# Schaltplan.net
KiCad netlist of a schematic drawn in EAGLE
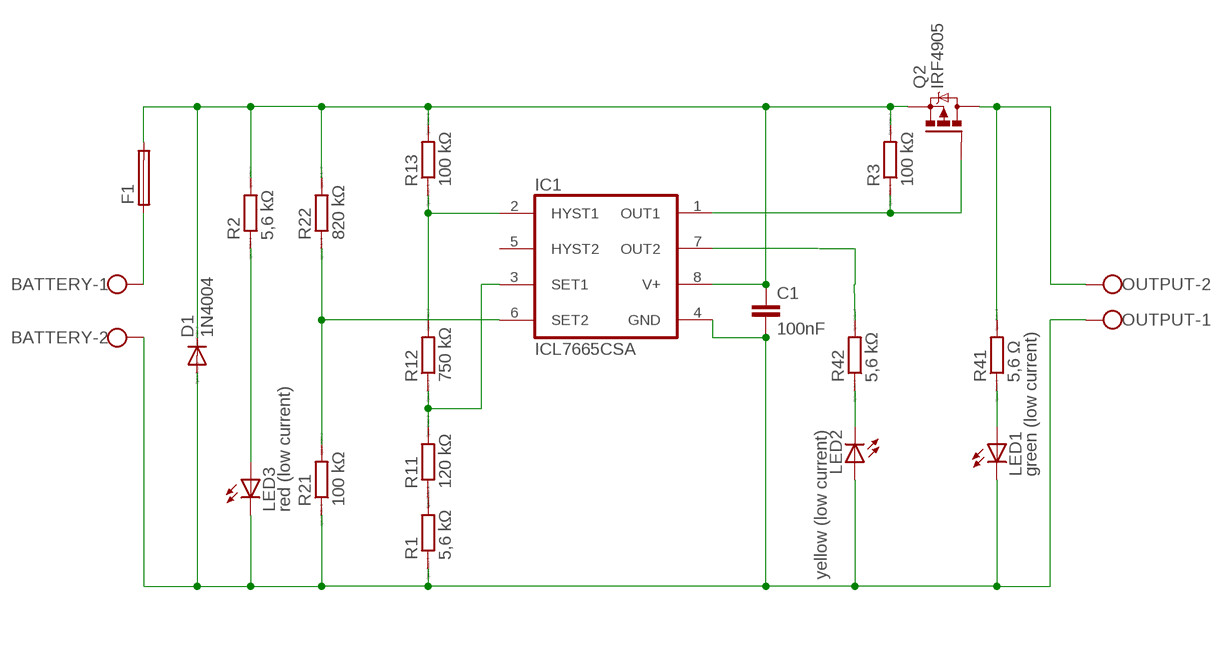
[diagram p0: schematic, sheet 1]

(export (version "E")
  (design (tool "Eeschema 10.0.6"))
  (components
    (comp (ref "BATTERY")
      (value "W237-102")
      (footprint "eagle-import:W237-102")
      (fields (field (name "MPN") "237-102"))
      (libsource (lib "eagle-import") (part "W237-102"))
    )
    (comp (ref "C1")
      (value "100nF")
      (footprint "eagle-import:C0603")
      (libsource (lib "eagle-import") (part "C-EUC0603"))
    )
    (comp (ref "D1")
      (value "1N4004")
      (footprint "eagle-import:DO41-10")
      (libsource (lib "eagle-import") (part "1N4004"))
    )
    (comp (ref "F1")
      (value "GSH15")
      (footprint "eagle-import:GSH15")
      (fields (field (name "MPN") "64900001039"))
      (libsource (lib "eagle-import") (part "GSH15"))
    )
    (comp (ref "IC1")
      (value "ICL7665CSA")
      (footprint "eagle-import:SO08")
      (fields (field (name "MPN") "ICL7665CSA+"))
      (libsource (lib "eagle-import") (part "ICL7665CSA"))
    )
    (comp (ref "LED1")
      (value "green (low current)")
      (footprint "eagle-import:SML0603")
      (libsource (lib "eagle-import") (part "LEDSML0603"))
    )
    (comp (ref "LED2")
      (value "yellow (low current)")
      (footprint "eagle-import:KA-3528ASYC")
      (libsource (lib "eagle-import") (part "LEDKA-3528ASYC"))
    )
    (comp (ref "LED3")
      (value "red (low current)")
      (footprint "eagle-import:KA-3528ASYC")
      (libsource (lib "eagle-import") (part "LEDKA-3528ASYC"))
    )
    (comp (ref "OUTPUT")
      (value "W237-102")
      (footprint "eagle-import:W237-102")
      (fields (field (name "MPN") "237-102"))
      (libsource (lib "eagle-import") (part "W237-102"))
    )
    (comp (ref "Q2")
      (value "IRF4905")
      (footprint "eagle-import:TO220BH")
      (libsource (lib "eagle-import") (part "IRF4905"))
    )
    (comp (ref "R1")
      (value "5,6 kΩ")
      (footprint "eagle-import:R1206")
      (libsource (lib "eagle-import") (part "RR1206"))
    )
    (comp (ref "R2")
      (value "5,6 kΩ")
      (footprint "eagle-import:R1206")
      (libsource (lib "eagle-import") (part "RR1206"))
    )
    (comp (ref "R3")
      (value "100 kΩ")
      (footprint "eagle-import:R1206")
      (libsource (lib "eagle-import") (part "RR1206"))
    )
    (comp (ref "R11")
      (value "120 kΩ")
      (footprint "eagle-import:R1206")
      (libsource (lib "eagle-import") (part "RR1206"))
    )
    (comp (ref "R12")
      (value "750 kΩ")
      (footprint "eagle-import:R1206")
      (libsource (lib "eagle-import") (part "RR1206"))
    )
    (comp (ref "R13")
      (value "100 kΩ")
      (footprint "eagle-import:R1206")
      (libsource (lib "eagle-import") (part "RR1206"))
    )
    (comp (ref "R21")
      (value "100 kΩ")
      (footprint "eagle-import:R1206")
      (libsource (lib "eagle-import") (part "RR1206"))
    )
    (comp (ref "R22")
      (value "820 kΩ")
      (footprint "eagle-import:R1206")
      (libsource (lib "eagle-import") (part "RR1206"))
    )
    (comp (ref "R41")
      (value "5,6 Ω")
      (footprint "eagle-import:R1206")
      (libsource (lib "eagle-import") (part "RR1206"))
    )
    (comp (ref "R42")
      (value "5,6 kΩ")
      (footprint "eagle-import:R1206")
      (libsource (lib "eagle-import") (part "RR1206"))
    )
  )
  (nets
    (net (code "1") (name "Net-(BATTERYA-KL)") (class "Default")
      (node (ref "BATTERY") (pin "1") (pinfunction "KL_1") (pintype "passive"))
      (node (ref "F1") (pin "1") (pinfunction "1_1") (pintype "passive"))
    )
    (net (code "2") (name "Net-(BATTERYB-KL)") (class "Default")
      (node (ref "BATTERY") (pin "2") (pinfunction "KL_2") (pintype "passive"))
      (node (ref "C1") (pin "2") (pinfunction "2_2") (pintype "passive"))
      (node (ref "D1") (pin "A") (pinfunction "A_A") (pintype "passive"))
      (node (ref "IC1") (pin "4") (pinfunction "GND_4") (pintype "power_in"))
      (node (ref "LED1") (pin "C") (pinfunction "C_C") (pintype "passive"))
      (node (ref "LED2") (pin "A") (pinfunction "A_A") (pintype "passive"))
      (node (ref "LED3") (pin "C") (pinfunction "C_C") (pintype "passive"))
      (node (ref "OUTPUT") (pin "1") (pinfunction "KL_1") (pintype "passive"))
      (node (ref "R1") (pin "1") (pinfunction "1_1") (pintype "passive"))
      (node (ref "R21") (pin "1") (pinfunction "1_1") (pintype "passive"))
    )
    (net (code "3") (name "Net-(IC1-HYST1)") (class "Default")
      (node (ref "IC1") (pin "2") (pinfunction "HYST1_2") (pintype "input"))
      (node (ref "R12") (pin "2") (pinfunction "2_2") (pintype "passive"))
      (node (ref "R13") (pin "1") (pinfunction "1_1") (pintype "passive"))
    )
    (net (code "4") (name "Net-(IC1-OUT1)") (class "Default")
      (node (ref "IC1") (pin "1") (pinfunction "OUT1_1") (pintype "output"))
      (node (ref "Q2") (pin "G") (pinfunction "G_G") (pintype "passive"))
      (node (ref "R3") (pin "1") (pinfunction "1_1") (pintype "passive"))
    )
    (net (code "5") (name "Net-(IC1-SET1)") (class "Default")
      (node (ref "IC1") (pin "3") (pinfunction "SET1_3") (pintype "input"))
      (node (ref "R11") (pin "2") (pinfunction "2_2") (pintype "passive"))
      (node (ref "R12") (pin "1") (pinfunction "1_1") (pintype "passive"))
    )
    (net (code "6") (name "Net-(IC1-SET2)") (class "Default")
      (node (ref "IC1") (pin "6") (pinfunction "SET2_6") (pintype "input"))
      (node (ref "R21") (pin "2") (pinfunction "2_2") (pintype "passive"))
      (node (ref "R22") (pin "1") (pinfunction "1_1") (pintype "passive"))
    )
    (net (code "7") (name "Net-(IC1-V+)") (class "Default")
      (node (ref "C1") (pin "1") (pinfunction "1_1") (pintype "passive"))
      (node (ref "D1") (pin "C") (pinfunction "C_C") (pintype "passive"))
      (node (ref "F1") (pin "2") (pinfunction "2_2") (pintype "passive"))
      (node (ref "IC1") (pin "8") (pinfunction "V+_8") (pintype "power_in"))
      (node (ref "Q2") (pin "S") (pinfunction "S_S") (pintype "passive"))
      (node (ref "R13") (pin "2") (pinfunction "2_2") (pintype "passive"))
      (node (ref "R2") (pin "2") (pinfunction "2_2") (pintype "passive"))
      (node (ref "R22") (pin "2") (pinfunction "2_2") (pintype "passive"))
      (node (ref "R3") (pin "2") (pinfunction "2_2") (pintype "passive"))
    )
    (net (code "8") (name "Net-(LED1-PadA)") (class "Default")
      (node (ref "LED1") (pin "A") (pinfunction "A_A") (pintype "passive"))
      (node (ref "R41") (pin "1") (pinfunction "1_1") (pintype "passive"))
    )
    (net (code "9") (name "Net-(LED2-PadC)") (class "Default")
      (node (ref "LED2") (pin "C") (pinfunction "C_C") (pintype "passive"))
      (node (ref "R42") (pin "1") (pinfunction "1_1") (pintype "passive"))
    )
    (net (code "10") (name "Net-(LED3-PadA)") (class "Default")
      (node (ref "LED3") (pin "A") (pinfunction "A_A") (pintype "passive"))
      (node (ref "R2") (pin "1") (pinfunction "1_1") (pintype "passive"))
    )
    (net (code "11") (name "Net-(OUTPUTB-KL)") (class "Default")
      (node (ref "OUTPUT") (pin "2") (pinfunction "KL_2") (pintype "passive"))
      (node (ref "Q2") (pin "D") (pinfunction "D_D") (pintype "passive"))
      (node (ref "R41") (pin "2") (pinfunction "2_2") (pintype "passive"))
    )
    (net (code "12") (name "Net-(R1-Pad2)") (class "Default")
      (node (ref "R1") (pin "2") (pinfunction "2_2") (pintype "passive"))
      (node (ref "R11") (pin "1") (pinfunction "1_1") (pintype "passive"))
    )
    (net (code "13") (name "unconnected-(IC1-HYST2-Pad5)") (class "Default")
      (node (ref "IC1") (pin "5") (pinfunction "HYST2_5") (pintype "input"))
    )
    (net (code "14") (name "unconnected-(IC1-OUT2-Pad7)") (class "Default")
      (node (ref "IC1") (pin "7") (pinfunction "OUT2_7") (pintype "output"))
    )
    (net (code "15") (name "unconnected-(R42-Pad2)") (class "Default")
      (node (ref "R42") (pin "2") (pinfunction "2_2") (pintype "passive"))
    )
  )
)
